# sensor.net
KiCad netlist of a schematic drawn in EAGLE
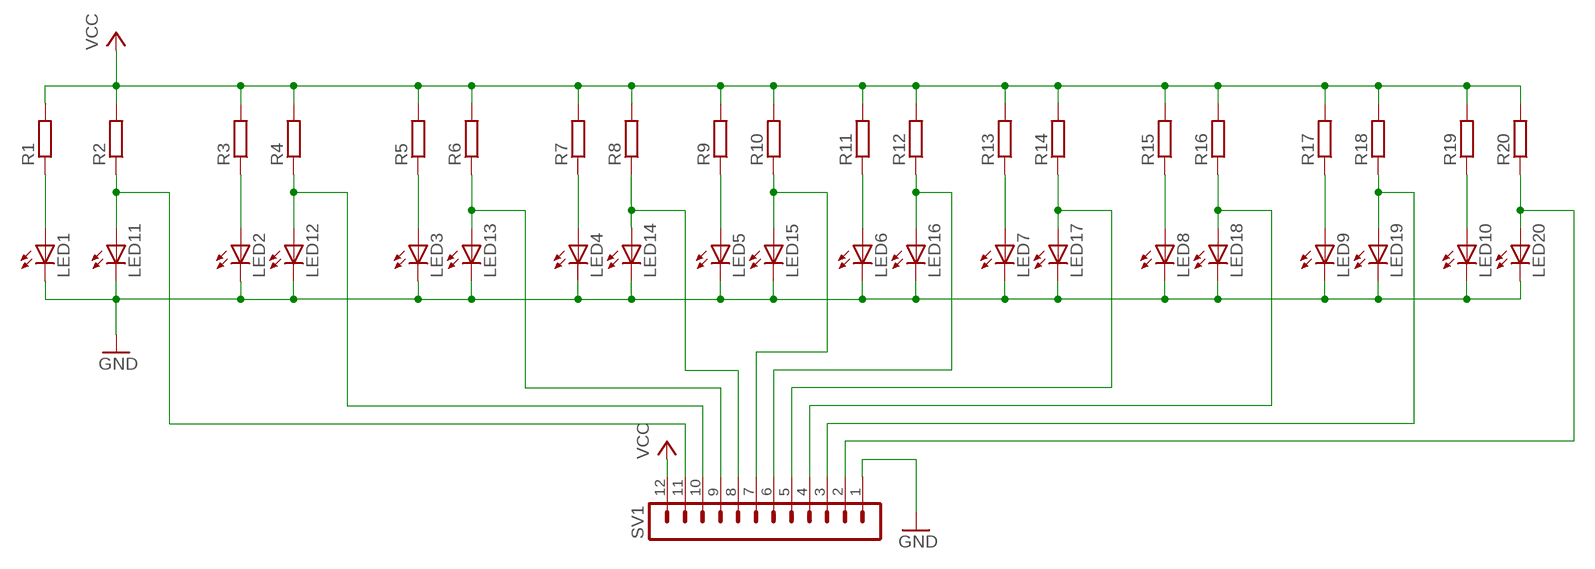
[diagram p0: schematic, sheet 1]

(export (version "E")
  (design (tool "Eeschema 10.0.6"))
  (components
    (comp (ref "LED1")
      (value "LED3MM")
      (footprint "eagle-import:LED3MM")
      (libsource (lib "eagle-import") (part "LED3MM"))
    )
    (comp (ref "LED2")
      (value "LED3MM")
      (footprint "eagle-import:LED3MM")
      (libsource (lib "eagle-import") (part "LED3MM"))
    )
    (comp (ref "LED3")
      (value "LED3MM")
      (footprint "eagle-import:LED3MM")
      (libsource (lib "eagle-import") (part "LED3MM"))
    )
    (comp (ref "LED4")
      (value "LED3MM")
      (footprint "eagle-import:LED3MM")
      (libsource (lib "eagle-import") (part "LED3MM"))
    )
    (comp (ref "LED5")
      (value "LED3MM")
      (footprint "eagle-import:LED3MM")
      (libsource (lib "eagle-import") (part "LED3MM"))
    )
    (comp (ref "LED6")
      (value "LED3MM")
      (footprint "eagle-import:LED3MM")
      (libsource (lib "eagle-import") (part "LED3MM"))
    )
    (comp (ref "LED7")
      (value "LED3MM")
      (footprint "eagle-import:LED3MM")
      (libsource (lib "eagle-import") (part "LED3MM"))
    )
    (comp (ref "LED8")
      (value "LED3MM")
      (footprint "eagle-import:LED3MM")
      (libsource (lib "eagle-import") (part "LED3MM"))
    )
    (comp (ref "LED9")
      (value "LED3MM")
      (footprint "eagle-import:LED3MM")
      (libsource (lib "eagle-import") (part "LED3MM"))
    )
    (comp (ref "LED10")
      (value "LED3MM")
      (footprint "eagle-import:LED3MM")
      (libsource (lib "eagle-import") (part "LED3MM"))
    )
    (comp (ref "LED11")
      (value "LED3MM")
      (footprint "eagle-import:LED3MM")
      (libsource (lib "eagle-import") (part "LED3MM"))
    )
    (comp (ref "LED12")
      (value "LED3MM")
      (footprint "eagle-import:LED3MM")
      (libsource (lib "eagle-import") (part "LED3MM"))
    )
    (comp (ref "LED13")
      (value "LED3MM")
      (footprint "eagle-import:LED3MM")
      (libsource (lib "eagle-import") (part "LED3MM"))
    )
    (comp (ref "LED14")
      (value "LED3MM")
      (footprint "eagle-import:LED3MM")
      (libsource (lib "eagle-import") (part "LED3MM"))
    )
    (comp (ref "LED15")
      (value "LED3MM")
      (footprint "eagle-import:LED3MM")
      (libsource (lib "eagle-import") (part "LED3MM"))
    )
    (comp (ref "LED16")
      (value "LED3MM")
      (footprint "eagle-import:LED3MM")
      (libsource (lib "eagle-import") (part "LED3MM"))
    )
    (comp (ref "LED17")
      (value "LED3MM")
      (footprint "eagle-import:LED3MM")
      (libsource (lib "eagle-import") (part "LED3MM"))
    )
    (comp (ref "LED18")
      (value "LED3MM")
      (footprint "eagle-import:LED3MM")
      (libsource (lib "eagle-import") (part "LED3MM"))
    )
    (comp (ref "LED19")
      (value "LED3MM")
      (footprint "eagle-import:LED3MM")
      (libsource (lib "eagle-import") (part "LED3MM"))
    )
    (comp (ref "LED20")
      (value "LED3MM")
      (footprint "eagle-import:LED3MM")
      (libsource (lib "eagle-import") (part "LED3MM"))
    )
    (comp (ref "R1")
      (value "R-EU_0207/7")
      (footprint "eagle-import:0207_7")
      (libsource (lib "eagle-import") (part "R-EU_0207/7"))
    )
    (comp (ref "R2")
      (value "R-EU_0207/7")
      (footprint "eagle-import:0207_7")
      (libsource (lib "eagle-import") (part "R-EU_0207/7"))
    )
    (comp (ref "R3")
      (value "R-EU_0207/7")
      (footprint "eagle-import:0207_7")
      (libsource (lib "eagle-import") (part "R-EU_0207/7"))
    )
    (comp (ref "R4")
      (value "R-EU_0207/7")
      (footprint "eagle-import:0207_7")
      (libsource (lib "eagle-import") (part "R-EU_0207/7"))
    )
    (comp (ref "R5")
      (value "R-EU_0207/7")
      (footprint "eagle-import:0207_7")
      (libsource (lib "eagle-import") (part "R-EU_0207/7"))
    )
    (comp (ref "R6")
      (value "R-EU_0207/7")
      (footprint "eagle-import:0207_7")
      (libsource (lib "eagle-import") (part "R-EU_0207/7"))
    )
    (comp (ref "R7")
      (value "R-EU_0207/7")
      (footprint "eagle-import:0207_7")
      (libsource (lib "eagle-import") (part "R-EU_0207/7"))
    )
    (comp (ref "R8")
      (value "R-EU_0207/7")
      (footprint "eagle-import:0207_7")
      (libsource (lib "eagle-import") (part "R-EU_0207/7"))
    )
    (comp (ref "R9")
      (value "R-EU_0207/7")
      (footprint "eagle-import:0207_7")
      (libsource (lib "eagle-import") (part "R-EU_0207/7"))
    )
    (comp (ref "R10")
      (value "R-EU_0207/7")
      (footprint "eagle-import:0207_7")
      (libsource (lib "eagle-import") (part "R-EU_0207/7"))
    )
    (comp (ref "R11")
      (value "R-EU_0207/7")
      (footprint "eagle-import:0207_7")
      (libsource (lib "eagle-import") (part "R-EU_0207/7"))
    )
    (comp (ref "R12")
      (value "R-EU_0207/7")
      (footprint "eagle-import:0207_7")
      (libsource (lib "eagle-import") (part "R-EU_0207/7"))
    )
    (comp (ref "R13")
      (value "R-EU_0207/7")
      (footprint "eagle-import:0207_7")
      (libsource (lib "eagle-import") (part "R-EU_0207/7"))
    )
    (comp (ref "R14")
      (value "R-EU_0207/7")
      (footprint "eagle-import:0207_7")
      (libsource (lib "eagle-import") (part "R-EU_0207/7"))
    )
    (comp (ref "R15")
      (value "R-EU_0207/7")
      (footprint "eagle-import:0207_7")
      (libsource (lib "eagle-import") (part "R-EU_0207/7"))
    )
    (comp (ref "R16")
      (value "R-EU_0207/7")
      (footprint "eagle-import:0207_7")
      (libsource (lib "eagle-import") (part "R-EU_0207/7"))
    )
    (comp (ref "R17")
      (value "R-EU_0207/7")
      (footprint "eagle-import:0207_7")
      (libsource (lib "eagle-import") (part "R-EU_0207/7"))
    )
    (comp (ref "R18")
      (value "R-EU_0207/7")
      (footprint "eagle-import:0207_7")
      (libsource (lib "eagle-import") (part "R-EU_0207/7"))
    )
    (comp (ref "R19")
      (value "R-EU_0207/7")
      (footprint "eagle-import:0207_7")
      (libsource (lib "eagle-import") (part "R-EU_0207/7"))
    )
    (comp (ref "R20")
      (value "R-EU_0207/7")
      (footprint "eagle-import:0207_7")
      (libsource (lib "eagle-import") (part "R-EU_0207/7"))
    )
    (comp (ref "SV1")
      (value "MA12-1")
      (footprint "eagle-import:MA12-1")
      (libsource (lib "eagle-import") (part "MA12-1"))
    )
  )
  (nets
    (net (code "1") (name "GND") (class "Default")
      (node (ref "LED1") (pin "K") (pinfunction "C_K") (pintype "passive"))
      (node (ref "LED10") (pin "K") (pinfunction "C_K") (pintype "passive"))
      (node (ref "LED11") (pin "K") (pinfunction "C_K") (pintype "passive"))
      (node (ref "LED12") (pin "K") (pinfunction "C_K") (pintype "passive"))
      (node (ref "LED13") (pin "K") (pinfunction "C_K") (pintype "passive"))
      (node (ref "LED14") (pin "K") (pinfunction "C_K") (pintype "passive"))
      (node (ref "LED15") (pin "K") (pinfunction "C_K") (pintype "passive"))
      (node (ref "LED16") (pin "K") (pinfunction "C_K") (pintype "passive"))
      (node (ref "LED17") (pin "K") (pinfunction "C_K") (pintype "passive"))
      (node (ref "LED18") (pin "K") (pinfunction "C_K") (pintype "passive"))
      (node (ref "LED19") (pin "K") (pinfunction "C_K") (pintype "passive"))
      (node (ref "LED2") (pin "K") (pinfunction "C_K") (pintype "passive"))
      (node (ref "LED20") (pin "K") (pinfunction "C_K") (pintype "passive"))
      (node (ref "LED3") (pin "K") (pinfunction "C_K") (pintype "passive"))
      (node (ref "LED4") (pin "K") (pinfunction "C_K") (pintype "passive"))
      (node (ref "LED5") (pin "K") (pinfunction "C_K") (pintype "passive"))
      (node (ref "LED6") (pin "K") (pinfunction "C_K") (pintype "passive"))
      (node (ref "LED7") (pin "K") (pinfunction "C_K") (pintype "passive"))
      (node (ref "LED8") (pin "K") (pinfunction "C_K") (pintype "passive"))
      (node (ref "LED9") (pin "K") (pinfunction "C_K") (pintype "passive"))
      (node (ref "SV1") (pin "1") (pinfunction "1_1") (pintype "passive"))
    )
    (net (code "2") (name "Net-(LED1-PadA)") (class "Default")
      (node (ref "LED1") (pin "A") (pinfunction "A_A") (pintype "passive"))
      (node (ref "R1") (pin "1") (pinfunction "1_1") (pintype "passive"))
    )
    (net (code "3") (name "Net-(LED2-PadA)") (class "Default")
      (node (ref "LED2") (pin "A") (pinfunction "A_A") (pintype "passive"))
      (node (ref "R3") (pin "1") (pinfunction "1_1") (pintype "passive"))
    )
    (net (code "4") (name "Net-(LED3-PadA)") (class "Default")
      (node (ref "LED3") (pin "A") (pinfunction "A_A") (pintype "passive"))
      (node (ref "R5") (pin "1") (pinfunction "1_1") (pintype "passive"))
    )
    (net (code "5") (name "Net-(LED4-PadA)") (class "Default")
      (node (ref "LED4") (pin "A") (pinfunction "A_A") (pintype "passive"))
      (node (ref "R7") (pin "1") (pinfunction "1_1") (pintype "passive"))
    )
    (net (code "6") (name "Net-(LED5-PadA)") (class "Default")
      (node (ref "LED5") (pin "A") (pinfunction "A_A") (pintype "passive"))
      (node (ref "R9") (pin "1") (pinfunction "1_1") (pintype "passive"))
    )
    (net (code "7") (name "Net-(LED6-PadA)") (class "Default")
      (node (ref "LED6") (pin "A") (pinfunction "A_A") (pintype "passive"))
      (node (ref "R11") (pin "1") (pinfunction "1_1") (pintype "passive"))
    )
    (net (code "8") (name "Net-(LED7-PadA)") (class "Default")
      (node (ref "LED7") (pin "A") (pinfunction "A_A") (pintype "passive"))
      (node (ref "R13") (pin "1") (pinfunction "1_1") (pintype "passive"))
    )
    (net (code "9") (name "Net-(LED8-PadA)") (class "Default")
      (node (ref "LED8") (pin "A") (pinfunction "A_A") (pintype "passive"))
      (node (ref "R15") (pin "1") (pinfunction "1_1") (pintype "passive"))
    )
    (net (code "10") (name "Net-(LED9-PadA)") (class "Default")
      (node (ref "LED9") (pin "A") (pinfunction "A_A") (pintype "passive"))
      (node (ref "R17") (pin "1") (pinfunction "1_1") (pintype "passive"))
    )
    (net (code "11") (name "Net-(LED10-PadA)") (class "Default")
      (node (ref "LED10") (pin "A") (pinfunction "A_A") (pintype "passive"))
      (node (ref "R19") (pin "1") (pinfunction "1_1") (pintype "passive"))
    )
    (net (code "12") (name "Net-(LED11-PadA)") (class "Default")
      (node (ref "LED11") (pin "A") (pinfunction "A_A") (pintype "passive"))
      (node (ref "R2") (pin "1") (pinfunction "1_1") (pintype "passive"))
      (node (ref "SV1") (pin "11") (pinfunction "11_11") (pintype "passive"))
    )
    (net (code "13") (name "Net-(LED12-PadA)") (class "Default")
      (node (ref "LED12") (pin "A") (pinfunction "A_A") (pintype "passive"))
      (node (ref "R4") (pin "1") (pinfunction "1_1") (pintype "passive"))
      (node (ref "SV1") (pin "10") (pinfunction "10_10") (pintype "passive"))
    )
    (net (code "14") (name "Net-(LED13-PadA)") (class "Default")
      (node (ref "LED13") (pin "A") (pinfunction "A_A") (pintype "passive"))
      (node (ref "R6") (pin "1") (pinfunction "1_1") (pintype "passive"))
      (node (ref "SV1") (pin "9") (pinfunction "9_9") (pintype "passive"))
    )
    (net (code "15") (name "Net-(LED14-PadA)") (class "Default")
      (node (ref "LED14") (pin "A") (pinfunction "A_A") (pintype "passive"))
      (node (ref "R8") (pin "1") (pinfunction "1_1") (pintype "passive"))
      (node (ref "SV1") (pin "8") (pinfunction "8_8") (pintype "passive"))
    )
    (net (code "16") (name "Net-(LED15-PadA)") (class "Default")
      (node (ref "LED15") (pin "A") (pinfunction "A_A") (pintype "passive"))
      (node (ref "R10") (pin "1") (pinfunction "1_1") (pintype "passive"))
      (node (ref "SV1") (pin "7") (pinfunction "7_7") (pintype "passive"))
    )
    (net (code "17") (name "Net-(LED16-PadA)") (class "Default")
      (node (ref "LED16") (pin "A") (pinfunction "A_A") (pintype "passive"))
      (node (ref "R12") (pin "1") (pinfunction "1_1") (pintype "passive"))
      (node (ref "SV1") (pin "6") (pinfunction "6_6") (pintype "passive"))
    )
    (net (code "18") (name "Net-(LED17-PadA)") (class "Default")
      (node (ref "LED17") (pin "A") (pinfunction "A_A") (pintype "passive"))
      (node (ref "R14") (pin "1") (pinfunction "1_1") (pintype "passive"))
      (node (ref "SV1") (pin "5") (pinfunction "5_5") (pintype "passive"))
    )
    (net (code "19") (name "Net-(LED18-PadA)") (class "Default")
      (node (ref "LED18") (pin "A") (pinfunction "A_A") (pintype "passive"))
      (node (ref "R16") (pin "1") (pinfunction "1_1") (pintype "passive"))
      (node (ref "SV1") (pin "4") (pinfunction "4_4") (pintype "passive"))
    )
    (net (code "20") (name "Net-(LED19-PadA)") (class "Default")
      (node (ref "LED19") (pin "A") (pinfunction "A_A") (pintype "passive"))
      (node (ref "R18") (pin "1") (pinfunction "1_1") (pintype "passive"))
      (node (ref "SV1") (pin "3") (pinfunction "3_3") (pintype "passive"))
    )
    (net (code "21") (name "Net-(LED20-PadA)") (class "Default")
      (node (ref "LED20") (pin "A") (pinfunction "A_A") (pintype "passive"))
      (node (ref "R20") (pin "1") (pinfunction "1_1") (pintype "passive"))
      (node (ref "SV1") (pin "2") (pinfunction "2_2") (pintype "passive"))
    )
    (net (code "22") (name "VCC") (class "Default")
      (node (ref "R1") (pin "2") (pinfunction "2_2") (pintype "passive"))
      (node (ref "R10") (pin "2") (pinfunction "2_2") (pintype "passive"))
      (node (ref "R11") (pin "2") (pinfunction "2_2") (pintype "passive"))
      (node (ref "R12") (pin "2") (pinfunction "2_2") (pintype "passive"))
      (node (ref "R13") (pin "2") (pinfunction "2_2") (pintype "passive"))
      (node (ref "R14") (pin "2") (pinfunction "2_2") (pintype "passive"))
      (node (ref "R15") (pin "2") (pinfunction "2_2") (pintype "passive"))
      (node (ref "R16") (pin "2") (pinfunction "2_2") (pintype "passive"))
      (node (ref "R17") (pin "2") (pinfunction "2_2") (pintype "passive"))
      (node (ref "R18") (pin "2") (pinfunction "2_2") (pintype "passive"))
      (node (ref "R19") (pin "2") (pinfunction "2_2") (pintype "passive"))
      (node (ref "R2") (pin "2") (pinfunction "2_2") (pintype "passive"))
      (node (ref "R20") (pin "2") (pinfunction "2_2") (pintype "passive"))
      (node (ref "R3") (pin "2") (pinfunction "2_2") (pintype "passive"))
      (node (ref "R4") (pin "2") (pinfunction "2_2") (pintype "passive"))
      (node (ref "R5") (pin "2") (pinfunction "2_2") (pintype "passive"))
      (node (ref "R6") (pin "2") (pinfunction "2_2") (pintype "passive"))
      (node (ref "R7") (pin "2") (pinfunction "2_2") (pintype "passive"))
      (node (ref "R8") (pin "2") (pinfunction "2_2") (pintype "passive"))
      (node (ref "R9") (pin "2") (pinfunction "2_2") (pintype "passive"))
      (node (ref "SV1") (pin "12") (pinfunction "12_12") (pintype "passive"))
    )
  )
)
